# IMU.net
KiCad netlist of a schematic drawn in Altium Designer
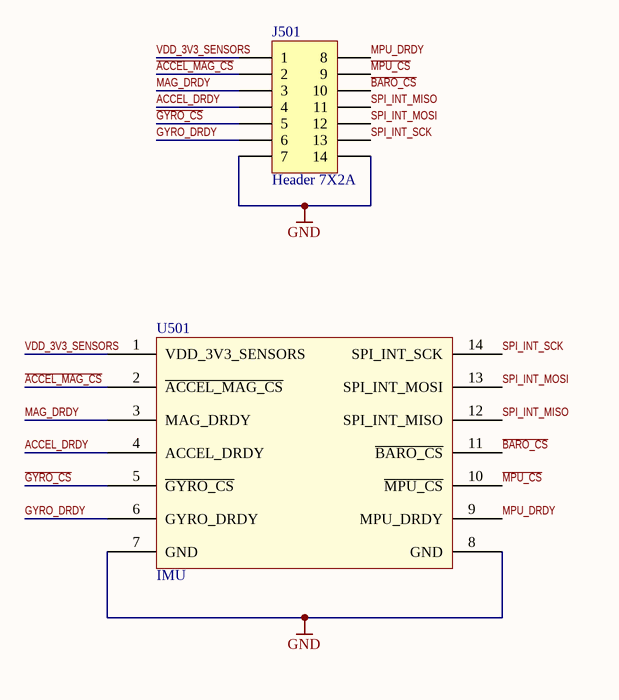
[diagram p0: IMU.SchDoc]

(export (version "E")
  (design (tool "Eeschema 10.0.6"))
  (components
    (comp (ref "J501")
      (value "Header 7X2A")
      (footprint "smt connecter1.27-15")
      (description "Header, 7-Pin, Dual row")
      (fields (field (name "PUBLISHER") "Altium Limited"))
      (libsource (lib "Miscellaneous Connectors") (part "Header 7X2A"))
    )
    (comp (ref "U501") (value "IMU") (footprint "IMU") (libsource (lib "PX4FMUv2.4.5_4") (part "IMU")))
  )
  (nets
    (net (code "1") (name "/ACCEL_DRDY") (class "Default")
      (node (ref "J501") (pin "4") (pinfunction "4_4") (pintype "passive"))
      (node (ref "U501") (pin "4") (pinfunction "ACCEL_DRDY_4") (pintype "passive"))
    )
    (net (code "2") (name "/GYRO_DRDY") (class "Default")
      (node (ref "J501") (pin "6") (pinfunction "6_6") (pintype "passive"))
      (node (ref "U501") (pin "6") (pinfunction "GYRO_DRDY_6") (pintype "passive"))
    )
    (net (code "3") (name "/MAG_DRDY") (class "Default")
      (node (ref "J501") (pin "3") (pinfunction "3_3") (pintype "passive"))
      (node (ref "U501") (pin "3") (pinfunction "MAG_DRDY_3") (pintype "passive"))
    )
    (net (code "4") (name "/MPU_DRDY") (class "Default")
      (node (ref "J501") (pin "8") (pinfunction "8_8") (pintype "passive"))
      (node (ref "U501") (pin "9") (pinfunction "MPU_DRDY_9") (pintype "passive"))
    )
    (net (code "5") (name "/SPI_INT_MISO") (class "Default")
      (node (ref "J501") (pin "11") (pinfunction "11_11") (pintype "passive"))
      (node (ref "U501") (pin "12") (pinfunction "SPI_INT_MISO_12") (pintype "passive"))
    )
    (net (code "6") (name "/SPI_INT_MOSI") (class "Default")
      (node (ref "J501") (pin "12") (pinfunction "12_12") (pintype "passive"))
      (node (ref "U501") (pin "13") (pinfunction "SPI_INT_MOSI_13") (pintype "passive"))
    )
    (net (code "7") (name "/SPI_INT_SCK") (class "Default")
      (node (ref "J501") (pin "13") (pinfunction "13_13") (pintype "passive"))
      (node (ref "U501") (pin "14") (pinfunction "SPI_INT_SCK_14") (pintype "passive"))
    )
    (net (code "8") (name "/VDD_3V3_SENSORS") (class "Default")
      (node (ref "J501") (pin "1") (pinfunction "1_1") (pintype "passive"))
      (node (ref "U501") (pin "1") (pinfunction "VDD_3V3_SENSORS_1") (pintype "passive"))
    )
    (net (code "9") (name "/~{ACCEL_MAG_CS}") (class "Default")
      (node (ref "J501") (pin "2") (pinfunction "2_2") (pintype "passive"))
      (node (ref "U501") (pin "2") (pinfunction "~{ACCEL_MAG_CS}_2") (pintype "passive"))
    )
    (net (code "10") (name "/~{BARO_CS}") (class "Default")
      (node (ref "J501") (pin "10") (pinfunction "10_10") (pintype "passive"))
      (node (ref "U501") (pin "11") (pinfunction "~{BARO_CS}_11") (pintype "passive"))
    )
    (net (code "11") (name "/~{GYRO_CS}") (class "Default")
      (node (ref "J501") (pin "5") (pinfunction "5_5") (pintype "passive"))
      (node (ref "U501") (pin "5") (pinfunction "~{GYRO_CS}_5") (pintype "passive"))
    )
    (net (code "12") (name "/~{MPU_CS}") (class "Default")
      (node (ref "J501") (pin "9") (pinfunction "9_9") (pintype "passive"))
      (node (ref "U501") (pin "10") (pinfunction "~{MPU_CS}_10") (pintype "passive"))
    )
    (net (code "13") (name "GND") (class "Default")
      (node (ref "J501") (pin "14") (pinfunction "14_14") (pintype "passive"))
      (node (ref "J501") (pin "7") (pinfunction "7_7") (pintype "passive"))
      (node (ref "U501") (pin "7") (pinfunction "GND_7") (pintype "passive"))
      (node (ref "U501") (pin "8") (pinfunction "GND_8") (pintype "passive"))
    )
  )
)
